# 2CAN_Peripherals.net
KiCad netlist of a schematic drawn in Altium Designer
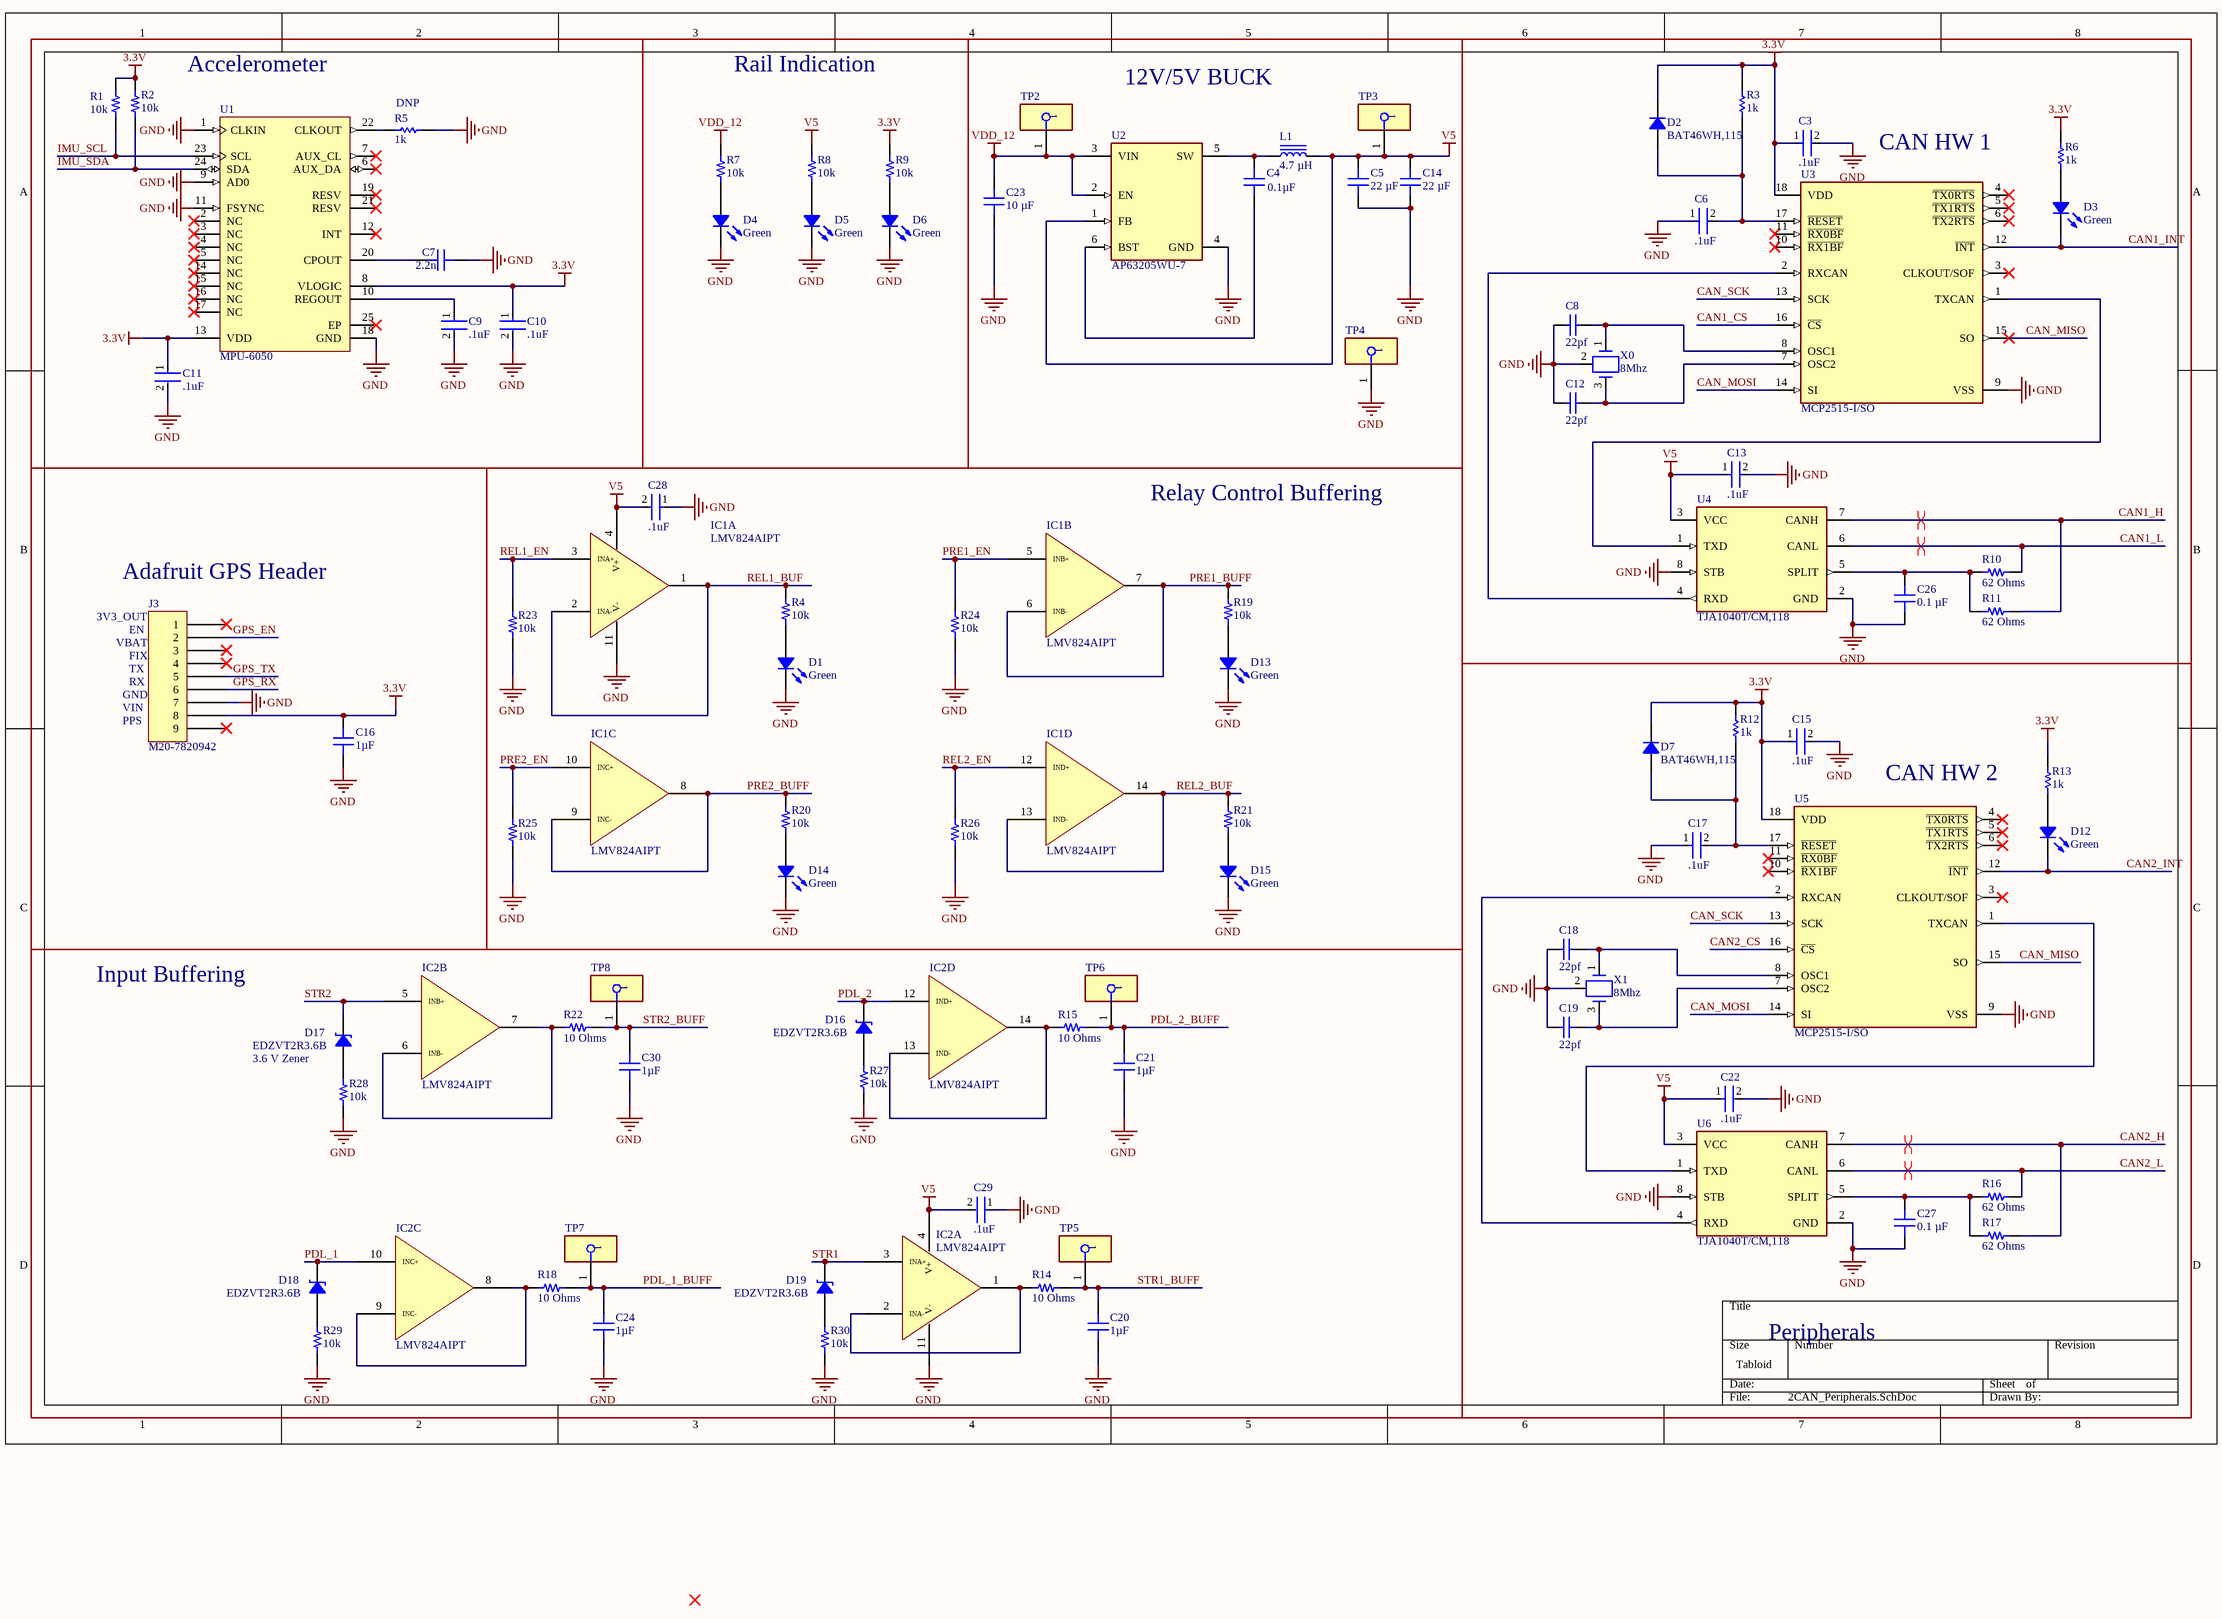
[diagram p0: 2CAN_Peripherals.SchDoc]

(export (version "E")
  (design (tool "Eeschema 10.0.6"))
  (components
    (comp (ref "C3")
      (value ".1uF")
      (footprint "FP-CGA3E-0_3-0_1-IPC_A")
      (description "Cap Ceramic 100nF 50V X7R 10% Pad SMD 0603 +125°C Automotive T/R")
      (fields (field (name "TOLERANCE") "10%") (field (name "VOLTAGE") "50V"))
      (libsource (lib "Altium Content Vault") (part "b4654b650e69147ec39a6b967a45e02"))
    )
    (comp (ref "C4")
      (value "0.1µF")
      (footprint "CAP 0603_1608")
      (description "CAP CER 0.1UF 50V X7R 0603")
      (fields (field (name "PART NUMBER") "06035C104JAT4A"))
      (libsource (lib "Celestial Altium Library - altium_library") (part "Capacitor"))
    )
    (comp (ref "C5")
      (value "22 µF")
      (footprint "CAP 0805_2012")
      (description "CAP CER 22UF 25V X5R 0805")
      (fields (field (name "PART NUMBER") "08053D226MAT2A") (field (name "MANUFACTURER") "KYOCERA AVX"))
      (libsource (lib "Celestial Altium Library - altium_library") (part "Capacitor"))
    )
    (comp (ref "C6")
      (value ".1uF")
      (footprint "FP-CGA3E-0_3-0_1-IPC_A")
      (description "Cap Ceramic 100nF 50V X7R 10% Pad SMD 0603 +125°C Automotive T/R")
      (fields (field (name "TOLERANCE") "10%") (field (name "VOLTAGE") "50V"))
      (libsource (lib "Altium Content Vault") (part "b4654b650e69147ec39a6b967a45e02"))
    )
    (comp (ref "C7")
      (value "2.2n")
      (footprint "CAP 0603_1608")
      (description "CAP CER 0603 2.2NF 16V X7R 10%")
      (fields (field (name "PART NUMBER") "C0603C222K4RECAUTO") (field (name "MANUFACTURER") "KEMET"))
      (libsource (lib "Celestial Altium Library - altium_library") (part "Capacitor"))
    )
    (comp (ref "C8")
      (value "22pf")
      (footprint "CAPC1608X90X35ML10T15")
      (description "Chip Capacitor, 22 pF, +/- 5%, 50 V, -55 to 125 degC, 0603 (1608 Metric), RoHS, Tape and Reel")
      (fields (field (name "MANUFACTURER") "Murata"))
      (libsource (lib "Altium Content Vault") (part "CAP-NP-2"))
    )
    (comp (ref "C9")
      (value ".1uF")
      (footprint "FP-CGA3E-0_3-0_1-IPC_A")
      (description "Cap Ceramic 100nF 50V X7R 10% Pad SMD 0603 +125°C Automotive T/R")
      (fields (field (name "TOLERANCE") "10%") (field (name "VOLTAGE") "50V"))
      (libsource (lib "Altium Content Vault") (part "b4654b650e69147ec39a6b967a45e02"))
    )
    (comp (ref "C10")
      (value ".1uF")
      (footprint "FP-CGA3E-0_3-0_1-IPC_A")
      (description "Cap Ceramic 100nF 50V X7R 10% Pad SMD 0603 +125°C Automotive T/R")
      (fields (field (name "TOLERANCE") "10%") (field (name "VOLTAGE") "50V"))
      (libsource (lib "Altium Content Vault") (part "b4654b650e69147ec39a6b967a45e02"))
    )
    (comp (ref "C11")
      (value ".1uF")
      (footprint "FP-CGA3E-0_3-0_1-IPC_A")
      (description "Cap Ceramic 100nF 50V X7R 10% Pad SMD 0603 +125°C Automotive T/R")
      (fields (field (name "TOLERANCE") "10%") (field (name "VOLTAGE") "50V"))
      (libsource (lib "Altium Content Vault") (part "b4654b650e69147ec39a6b967a45e02"))
    )
    (comp (ref "C12")
      (value "22pf")
      (footprint "CAPC1608X90X35ML10T15")
      (description "Chip Capacitor, 22 pF, +/- 5%, 50 V, -55 to 125 degC, 0603 (1608 Metric), RoHS, Tape and Reel")
      (fields (field (name "MANUFACTURER") "Murata"))
      (libsource (lib "Altium Content Vault") (part "CAP-NP-2"))
    )
    (comp (ref "C13")
      (value ".1uF")
      (footprint "FP-CGA3E-0_3-0_1-IPC_A")
      (description "Cap Ceramic 100nF 50V X7R 10% Pad SMD 0603 +125°C Automotive T/R")
      (fields (field (name "TOLERANCE") "10%") (field (name "VOLTAGE") "50V"))
      (libsource (lib "Altium Content Vault") (part "b4654b650e69147ec39a6b967a45e02"))
    )
    (comp (ref "C14")
      (value "22 µF")
      (footprint "CAP 0805_2012")
      (description "CAP CER 22UF 25V X5R 0805")
      (fields (field (name "PART NUMBER") "08053D226MAT2A") (field (name "MANUFACTURER") "KYOCERA AVX"))
      (libsource (lib "Celestial Altium Library - altium_library") (part "Capacitor"))
    )
    (comp (ref "C15")
      (value ".1uF")
      (footprint "FP-CGA3E-0_3-0_1-IPC_A")
      (description "Cap Ceramic 100nF 50V X7R 10% Pad SMD 0603 +125°C Automotive T/R")
      (fields (field (name "TOLERANCE") "10%") (field (name "VOLTAGE") "50V"))
      (libsource (lib "Altium Content Vault") (part "b4654b650e69147ec39a6b967a45e02"))
    )
    (comp (ref "C16")
      (value "1µF")
      (footprint "CAP 0603_1608")
      (description "CAP CER 1UF 25V X5R 0603")
      (fields (field (name "PART NUMBER") "06033D105MAT2A") (field (name "MANUFACTURER") "AVX Corporation"))
      (libsource (lib "Celestial Altium Library - altium_library") (part "Capacitor"))
    )
    (comp (ref "C17")
      (value ".1uF")
      (footprint "FP-CGA3E-0_3-0_1-IPC_A")
      (description "Cap Ceramic 100nF 50V X7R 10% Pad SMD 0603 +125°C Automotive T/R")
      (fields (field (name "TOLERANCE") "10%") (field (name "VOLTAGE") "50V"))
      (libsource (lib "Altium Content Vault") (part "b4654b650e69147ec39a6b967a45e02"))
    )
    (comp (ref "C18")
      (value "22pf")
      (footprint "CAPC1608X90X35ML10T15")
      (description "Chip Capacitor, 22 pF, +/- 5%, 50 V, -55 to 125 degC, 0603 (1608 Metric), RoHS, Tape and Reel")
      (fields (field (name "MANUFACTURER") "Murata"))
      (libsource (lib "Altium Content Vault") (part "CAP-NP-2"))
    )
    (comp (ref "C19")
      (value "22pf")
      (footprint "CAPC1608X90X35ML10T15")
      (description "Chip Capacitor, 22 pF, +/- 5%, 50 V, -55 to 125 degC, 0603 (1608 Metric), RoHS, Tape and Reel")
      (fields (field (name "MANUFACTURER") "Murata"))
      (libsource (lib "Altium Content Vault") (part "CAP-NP-2"))
    )
    (comp (ref "C20")
      (value "1µF")
      (footprint "CAP 0603_1608")
      (description "CAP CER 1UF 25V X5R 0603")
      (fields (field (name "PART NUMBER") "06033D105MAT2A") (field (name "MANUFACTURER") "AVX Corporation"))
      (libsource (lib "Celestial Altium Library - altium_library") (part "Capacitor"))
    )
    (comp (ref "C21")
      (value "1µF")
      (footprint "CAP 0603_1608")
      (description "CAP CER 1UF 25V X5R 0603")
      (fields (field (name "PART NUMBER") "06033D105MAT2A") (field (name "MANUFACTURER") "AVX Corporation"))
      (libsource (lib "Celestial Altium Library - altium_library") (part "Capacitor"))
    )
    (comp (ref "C22")
      (value ".1uF")
      (footprint "FP-CGA3E-0_3-0_1-IPC_A")
      (description "Cap Ceramic 100nF 50V X7R 10% Pad SMD 0603 +125°C Automotive T/R")
      (fields (field (name "TOLERANCE") "10%") (field (name "VOLTAGE") "50V"))
      (libsource (lib "Altium Content Vault") (part "b4654b650e69147ec39a6b967a45e02"))
    )
    (comp (ref "C23")
      (value "10 µF")
      (footprint "CAP 0805_2012")
      (description "CAP CER 10UF 50V X5R 0805")
      (fields
        (field (name "PART NUMBER") "GRM21BR61H106KE43L")
        (field (name "MANUFACTURER") "Murata Electronics")
      )
      (libsource (lib "Celestial Altium Library - altium_library") (part "Capacitor"))
    )
    (comp (ref "C24")
      (value "1µF")
      (footprint "CAP 0603_1608")
      (description "CAP CER 1UF 25V X5R 0603")
      (fields (field (name "PART NUMBER") "06033D105MAT2A") (field (name "MANUFACTURER") "AVX Corporation"))
      (libsource (lib "Celestial Altium Library - altium_library") (part "Capacitor"))
    )
    (comp (ref "C26")
      (value "0.1 µF")
      (footprint "CAP 0603_1608")
      (description "CAP CER 0.1UF 100V X7R 0603")
      (fields (field (name "PART NUMBER") "HMK107B7104KA-T") (field (name "MANUFACTURER") "Taiyo Yuden"))
      (libsource (lib "Celestial Altium Library - altium_library") (part "Capacitor"))
    )
    (comp (ref "C27")
      (value "0.1 µF")
      (footprint "CAP 0603_1608")
      (description "CAP CER 0.1UF 100V X7R 0603")
      (fields (field (name "PART NUMBER") "HMK107B7104KA-T") (field (name "MANUFACTURER") "Taiyo Yuden"))
      (libsource (lib "Celestial Altium Library - altium_library") (part "Capacitor"))
    )
    (comp (ref "C28")
      (value ".1uF")
      (footprint "FP-CGA3E-0_3-0_1-IPC_A")
      (description "Cap Ceramic 100nF 50V X7R 10% Pad SMD 0603 +125°C Automotive T/R")
      (fields (field (name "TOLERANCE") "10%") (field (name "VOLTAGE") "50V"))
      (libsource (lib "Altium Content Vault") (part "b4654b650e69147ec39a6b967a45e02"))
    )
    (comp (ref "C29")
      (value ".1uF")
      (footprint "FP-CGA3E-0_3-0_1-IPC_A")
      (description "Cap Ceramic 100nF 50V X7R 10% Pad SMD 0603 +125°C Automotive T/R")
      (fields (field (name "TOLERANCE") "10%") (field (name "VOLTAGE") "50V"))
      (libsource (lib "Altium Content Vault") (part "b4654b650e69147ec39a6b967a45e02"))
    )
    (comp (ref "C30")
      (value "1µF")
      (footprint "CAP 0603_1608")
      (description "CAP CER 1UF 25V X5R 0603")
      (fields (field (name "PART NUMBER") "06033D105MAT2A") (field (name "MANUFACTURER") "AVX Corporation"))
      (libsource (lib "Celestial Altium Library - altium_library") (part "Capacitor"))
    )
    (comp (ref "D1")
      (value "Green")
      (footprint "LED 0603_1608 GREEN")
      (description "LED GREEN DIFFUSED SMD")
      (fields
        (field (name "PART NUMBER") "SML-LX0603GW-TR")
        (field (name "MANUFACTURER") "Lumex Opto/Components Inc.")
      )
      (libsource (lib "Celestial Altium Library - altium_library") (part "LED"))
    )
    (comp (ref "D2")
      (value "BAT46WH,115")
      (footprint "SOD123F")
      (description "DIODE SCHOTT 100V 250MA SOD123F")
      (fields (field (name "MANUFACTURER") "Nexperia USA Inc."))
      (libsource (lib "Celestial Altium Library - altium_library") (part "Diode"))
    )
    (comp (ref "D3")
      (value "Green")
      (footprint "LED 0603_1608 GREEN")
      (description "LED GREEN DIFFUSED SMD")
      (fields
        (field (name "PART NUMBER") "SML-LX0603GW-TR")
        (field (name "MANUFACTURER") "Lumex Opto/Components Inc.")
      )
      (libsource (lib "Celestial Altium Library - altium_library") (part "LED"))
    )
    (comp (ref "D4")
      (value "Green")
      (footprint "LED 0603_1608 GREEN")
      (description "LED GREEN DIFFUSED SMD")
      (fields
        (field (name "PART NUMBER") "SML-LX0603GW-TR")
        (field (name "MANUFACTURER") "Lumex Opto/Components Inc.")
      )
      (libsource (lib "Celestial Altium Library - altium_library") (part "LED"))
    )
    (comp (ref "D5")
      (value "Green")
      (footprint "LED 0603_1608 GREEN")
      (description "LED GREEN DIFFUSED SMD")
      (fields
        (field (name "PART NUMBER") "SML-LX0603GW-TR")
        (field (name "MANUFACTURER") "Lumex Opto/Components Inc.")
      )
      (libsource (lib "Celestial Altium Library - altium_library") (part "LED"))
    )
    (comp (ref "D6")
      (value "Green")
      (footprint "LED 0603_1608 GREEN")
      (description "LED GREEN DIFFUSED SMD")
      (fields
        (field (name "PART NUMBER") "SML-LX0603GW-TR")
        (field (name "MANUFACTURER") "Lumex Opto/Components Inc.")
      )
      (libsource (lib "Celestial Altium Library - altium_library") (part "LED"))
    )
    (comp (ref "D7")
      (value "BAT46WH,115")
      (footprint "SOD123F")
      (description "DIODE SCHOTT 100V 250MA SOD123F")
      (fields (field (name "MANUFACTURER") "Nexperia USA Inc."))
      (libsource (lib "Celestial Altium Library - altium_library") (part "Diode"))
    )
    (comp (ref "D12")
      (value "Green")
      (footprint "LED 0603_1608 GREEN")
      (description "LED GREEN DIFFUSED SMD")
      (fields
        (field (name "PART NUMBER") "SML-LX0603GW-TR")
        (field (name "MANUFACTURER") "Lumex Opto/Components Inc.")
      )
      (libsource (lib "Celestial Altium Library - altium_library") (part "LED"))
    )
    (comp (ref "D13")
      (value "Green")
      (footprint "LED 0603_1608 GREEN")
      (description "LED GREEN DIFFUSED SMD")
      (fields
        (field (name "PART NUMBER") "SML-LX0603GW-TR")
        (field (name "MANUFACTURER") "Lumex Opto/Components Inc.")
      )
      (libsource (lib "Celestial Altium Library - altium_library") (part "LED"))
    )
    (comp (ref "D14")
      (value "Green")
      (footprint "LED 0603_1608 GREEN")
      (description "LED GREEN DIFFUSED SMD")
      (fields
        (field (name "PART NUMBER") "SML-LX0603GW-TR")
        (field (name "MANUFACTURER") "Lumex Opto/Components Inc.")
      )
      (libsource (lib "Celestial Altium Library - altium_library") (part "LED"))
    )
    (comp (ref "D15")
      (value "Green")
      (footprint "LED 0603_1608 GREEN")
      (description "LED GREEN DIFFUSED SMD")
      (fields
        (field (name "PART NUMBER") "SML-LX0603GW-TR")
        (field (name "MANUFACTURER") "Lumex Opto/Components Inc.")
      )
      (libsource (lib "Celestial Altium Library - altium_library") (part "LED"))
    )
    (comp (ref "D16")
      (value "EDZVT2R3.6B")
      (footprint "SOD523F")
      (description "DIODE ZENER 3.6V 150MW EMD2")
      (fields (field (name "MANUFACTURER") "Rohm Semiconductor") (field (name "TOLERANCE") "±3%"))
      (libsource (lib "Celestial Altium Library - altium_library") (part "Diode Zener"))
    )
    (comp (ref "D17")
      (value "EDZVT2R3.6B")
      (footprint "SOD523F")
      (description "DIODE ZENER 3.6V 150MW EMD2")
      (fields (field (name "MANUFACTURER") "Rohm Semiconductor") (field (name "TOLERANCE") "±3%"))
      (libsource (lib "Celestial Altium Library - altium_library") (part "Diode Zener"))
    )
    (comp (ref "D18")
      (value "EDZVT2R3.6B")
      (footprint "SOD523F")
      (description "DIODE ZENER 3.6V 150MW EMD2")
      (fields (field (name "MANUFACTURER") "Rohm Semiconductor") (field (name "TOLERANCE") "±3%"))
      (libsource (lib "Celestial Altium Library - altium_library") (part "Diode Zener"))
    )
    (comp (ref "D19")
      (value "EDZVT2R3.6B")
      (footprint "SOD523F")
      (description "DIODE ZENER 3.6V 150MW EMD2")
      (fields (field (name "MANUFACTURER") "Rohm Semiconductor") (field (name "TOLERANCE") "±3%"))
      (libsource (lib "Celestial Altium Library - altium_library") (part "Diode Zener"))
    )
    (comp (ref "IC1")
      (value "LMV824AIPT")
      (footprint "TI TSSOP-14 PW")
      (description "IC OPAMP GP 4 CIRCUIT 14TSSOP")
      (fields (field (name "MANUFACTURER") "STMicroelectronics"))
      (libsource (lib "Celestial Altium Library - altium_library") (part "TI LMV82x 14 PIN"))
    )
    (comp (ref "IC2")
      (value "LMV824AIPT")
      (footprint "TI TSSOP-14 PW")
      (description "IC OPAMP GP 4 CIRCUIT 14TSSOP")
      (fields (field (name "MANUFACTURER") "STMicroelectronics"))
      (libsource (lib "Celestial Altium Library - altium_library") (part "TI LMV82x 14 PIN"))
    )
    (comp (ref "J3")
      (value "M20-7820942")
      (footprint "HARWIN M20-7820945")
      (description "CONN RCPT 9POS 0.1 GOLD PCB")
      (fields (field (name "MANUFACTURER") "Harwin Inc."))
      (libsource (lib "Celestial Altium Library - altium_library") (part "9 Pin"))
    )
    (comp (ref "L1")
      (value "4.7 µH")
      (footprint "WURTH WE-LQS 6045")
      (description "FIXED IND 4.7UH 3.3A 26 MOHM SMD")
      (fields (field (name "PART NUMBER") "74404064047") (field (name "MANUFACTURER") "Würth Elektronik"))
      (libsource (lib "Celestial Altium Library - altium_library") (part "Inductor"))
    )
    (comp (ref "R1")
      (value "10k")
      (footprint "RES 0603_1608")
      (description "RES SMD 10K OHM 0.1% 1/16W 0603")
      (fields
        (field (name "PART NUMBER") "CPF0603B10KE")
        (field (name "MANUFACTURER") "TE Connectivity Passive Product")
      )
      (libsource (lib "Celestial Altium Library - altium_library") (part "Resistor"))
    )
    (comp (ref "R2")
      (value "10k")
      (footprint "RES 0603_1608")
      (description "RES SMD 10K OHM 0.1% 1/16W 0603")
      (fields
        (field (name "PART NUMBER") "CPF0603B10KE")
        (field (name "MANUFACTURER") "TE Connectivity Passive Product")
      )
      (libsource (lib "Celestial Altium Library - altium_library") (part "Resistor"))
    )
    (comp (ref "R3")
      (value "1k")
      (footprint "RESC1608X55X30LL15T15")
      (fields (field (name "PART NUMBER") "ERJ-3EKF1001V") (field (name "MANUFACTURER") "Panasonic"))
      (libsource (lib "Altium Content Vault") (part "RES"))
    )
    (comp (ref "R4")
      (value "10k")
      (footprint "RES 0603_1608")
      (description "RES SMD 10K OHM 0.1% 1/16W 0603")
      (fields
        (field (name "PART NUMBER") "CPF0603B10KE")
        (field (name "MANUFACTURER") "TE Connectivity Passive Product")
      )
      (libsource (lib "Celestial Altium Library - altium_library") (part "Resistor"))
    )
    (comp (ref "R5")
      (value "1k")
      (footprint "RESC1608X55X30LL15T15")
      (fields (field (name "PART NUMBER") "ERJ-3EKF1001V") (field (name "MANUFACTURER") "Panasonic"))
      (libsource (lib "Altium Content Vault") (part "RES"))
    )
    (comp (ref "R6")
      (value "1k")
      (footprint "RESC1608X55X30LL15T15")
      (fields (field (name "PART NUMBER") "ERJ-3EKF1001V") (field (name "MANUFACTURER") "Panasonic"))
      (libsource (lib "Altium Content Vault") (part "RES"))
    )
    (comp (ref "R7")
      (value "10k")
      (footprint "RES 0603_1608")
      (description "RES SMD 10K OHM 0.1% 1/16W 0603")
      (fields
        (field (name "PART NUMBER") "CPF0603B10KE")
        (field (name "MANUFACTURER") "TE Connectivity Passive Product")
      )
      (libsource (lib "Celestial Altium Library - altium_library") (part "Resistor"))
    )
    (comp (ref "R8")
      (value "10k")
      (footprint "RES 0603_1608")
      (description "RES SMD 10K OHM 0.1% 1/16W 0603")
      (fields
        (field (name "PART NUMBER") "CPF0603B10KE")
        (field (name "MANUFACTURER") "TE Connectivity Passive Product")
      )
      (libsource (lib "Celestial Altium Library - altium_library") (part "Resistor"))
    )
    (comp (ref "R9")
      (value "10k")
      (footprint "RES 0603_1608")
      (description "RES SMD 10K OHM 0.1% 1/16W 0603")
      (fields
        (field (name "PART NUMBER") "CPF0603B10KE")
        (field (name "MANUFACTURER") "TE Connectivity Passive Product")
      )
      (libsource (lib "Celestial Altium Library - altium_library") (part "Resistor"))
    )
    (comp (ref "R10")
      (value "62 Ohms")
      (footprint "RES 0603_1608")
      (description "HIGH ANTI-SURGE THICK FILM CHIP")
      (fields (field (name "PART NUMBER") "SDR03EZPJ620") (field (name "MANUFACTURER") "Rohm Semiconductor"))
      (libsource (lib "Celestial Altium Library - altium_library") (part "Resistor"))
    )
    (comp (ref "R11")
      (value "62 Ohms")
      (footprint "RES 0603_1608")
      (description "HIGH ANTI-SURGE THICK FILM CHIP")
      (fields (field (name "PART NUMBER") "SDR03EZPJ620") (field (name "MANUFACTURER") "Rohm Semiconductor"))
      (libsource (lib "Celestial Altium Library - altium_library") (part "Resistor"))
    )
    (comp (ref "R12")
      (value "1k")
      (footprint "RESC1608X55X30LL15T15")
      (fields (field (name "PART NUMBER") "ERJ-3EKF1001V") (field (name "MANUFACTURER") "Panasonic"))
      (libsource (lib "Altium Content Vault") (part "RES"))
    )
    (comp (ref "R13")
      (value "1k")
      (footprint "RESC1608X55X30LL15T15")
      (fields (field (name "PART NUMBER") "ERJ-3EKF1001V") (field (name "MANUFACTURER") "Panasonic"))
      (libsource (lib "Altium Content Vault") (part "RES"))
    )
    (comp (ref "R14")
      (value "10 Ohms")
      (footprint "RES 0603_1608")
      (description "RESA-AS 0603 10R 1% 100MW TC100")
      (fields (field (name "PART NUMBER") "CR0603AFX-10R0EAS") (field (name "MANUFACTURER") "Bourns Inc."))
      (libsource (lib "Celestial Altium Library - altium_library") (part "Resistor"))
    )
    (comp (ref "R15")
      (value "10 Ohms")
      (footprint "RES 0603_1608")
      (description "RESA-AS 0603 10R 1% 100MW TC100")
      (fields (field (name "PART NUMBER") "CR0603AFX-10R0EAS") (field (name "MANUFACTURER") "Bourns Inc."))
      (libsource (lib "Celestial Altium Library - altium_library") (part "Resistor"))
    )
    (comp (ref "R16")
      (value "62 Ohms")
      (footprint "RES 0603_1608")
      (description "HIGH ANTI-SURGE THICK FILM CHIP")
      (fields (field (name "PART NUMBER") "SDR03EZPJ620") (field (name "MANUFACTURER") "Rohm Semiconductor"))
      (libsource (lib "Celestial Altium Library - altium_library") (part "Resistor"))
    )
    (comp (ref "R17")
      (value "62 Ohms")
      (footprint "RES 0603_1608")
      (description "HIGH ANTI-SURGE THICK FILM CHIP")
      (fields (field (name "PART NUMBER") "SDR03EZPJ620") (field (name "MANUFACTURER") "Rohm Semiconductor"))
      (libsource (lib "Celestial Altium Library - altium_library") (part "Resistor"))
    )
    (comp (ref "R18")
      (value "10 Ohms")
      (footprint "RES 0603_1608")
      (description "RESA-AS 0603 10R 1% 100MW TC100")
      (fields (field (name "PART NUMBER") "CR0603AFX-10R0EAS") (field (name "MANUFACTURER") "Bourns Inc."))
      (libsource (lib "Celestial Altium Library - altium_library") (part "Resistor"))
    )
    (comp (ref "R19")
      (value "10k")
      (footprint "RES 0603_1608")
      (description "RES SMD 10K OHM 0.1% 1/16W 0603")
      (fields
        (field (name "PART NUMBER") "CPF0603B10KE")
        (field (name "MANUFACTURER") "TE Connectivity Passive Product")
      )
      (libsource (lib "Celestial Altium Library - altium_library") (part "Resistor"))
    )
    (comp (ref "R20")
      (value "10k")
      (footprint "RES 0603_1608")
      (description "RES SMD 10K OHM 0.1% 1/16W 0603")
      (fields
        (field (name "PART NUMBER") "CPF0603B10KE")
        (field (name "MANUFACTURER") "TE Connectivity Passive Product")
      )
      (libsource (lib "Celestial Altium Library - altium_library") (part "Resistor"))
    )
    (comp (ref "R21")
      (value "10k")
      (footprint "RES 0603_1608")
      (description "RES SMD 10K OHM 0.1% 1/16W 0603")
      (fields
        (field (name "PART NUMBER") "CPF0603B10KE")
        (field (name "MANUFACTURER") "TE Connectivity Passive Product")
      )
      (libsource (lib "Celestial Altium Library - altium_library") (part "Resistor"))
    )
    (comp (ref "R22")
      (value "10 Ohms")
      (footprint "RES 0603_1608")
      (description "RESA-AS 0603 10R 1% 100MW TC100")
      (fields (field (name "PART NUMBER") "CR0603AFX-10R0EAS") (field (name "MANUFACTURER") "Bourns Inc."))
      (libsource (lib "Celestial Altium Library - altium_library") (part "Resistor"))
    )
    (comp (ref "R23")
      (value "10k")
      (footprint "RES 0603_1608")
      (description "RES SMD 10K OHM 0.1% 1/16W 0603")
      (fields
        (field (name "PART NUMBER") "CPF0603B10KE")
        (field (name "MANUFACTURER") "TE Connectivity Passive Product")
      )
      (libsource (lib "Celestial Altium Library - altium_library") (part "Resistor"))
    )
    (comp (ref "R24")
      (value "10k")
      (footprint "RES 0603_1608")
      (description "RES SMD 10K OHM 0.1% 1/16W 0603")
      (fields
        (field (name "PART NUMBER") "CPF0603B10KE")
        (field (name "MANUFACTURER") "TE Connectivity Passive Product")
      )
      (libsource (lib "Celestial Altium Library - altium_library") (part "Resistor"))
    )
    (comp (ref "R25")
      (value "10k")
      (footprint "RES 0603_1608")
      (description "RES SMD 10K OHM 0.1% 1/16W 0603")
      (fields
        (field (name "PART NUMBER") "CPF0603B10KE")
        (field (name "MANUFACTURER") "TE Connectivity Passive Product")
      )
      (libsource (lib "Celestial Altium Library - altium_library") (part "Resistor"))
    )
    (comp (ref "R26")
      (value "10k")
      (footprint "RES 0603_1608")
      (description "RES SMD 10K OHM 0.1% 1/16W 0603")
      (fields
        (field (name "PART NUMBER") "CPF0603B10KE")
        (field (name "MANUFACTURER") "TE Connectivity Passive Product")
      )
      (libsource (lib "Celestial Altium Library - altium_library") (part "Resistor"))
    )
    (comp (ref "R27")
      (value "10k")
      (footprint "RES 0603_1608")
      (description "RES SMD 10K OHM 0.1% 1/16W 0603")
      (fields
        (field (name "PART NUMBER") "CPF0603B10KE")
        (field (name "MANUFACTURER") "TE Connectivity Passive Product")
      )
      (libsource (lib "Celestial Altium Library - altium_library") (part "Resistor"))
    )
    (comp (ref "R28")
      (value "10k")
      (footprint "RES 0603_1608")
      (description "RES SMD 10K OHM 0.1% 1/16W 0603")
      (fields
        (field (name "PART NUMBER") "CPF0603B10KE")
        (field (name "MANUFACTURER") "TE Connectivity Passive Product")
      )
      (libsource (lib "Celestial Altium Library - altium_library") (part "Resistor"))
    )
    (comp (ref "R29")
      (value "10k")
      (footprint "RES 0603_1608")
      (description "RES SMD 10K OHM 0.1% 1/16W 0603")
      (fields
        (field (name "PART NUMBER") "CPF0603B10KE")
        (field (name "MANUFACTURER") "TE Connectivity Passive Product")
      )
      (libsource (lib "Celestial Altium Library - altium_library") (part "Resistor"))
    )
    (comp (ref "R30")
      (value "10k")
      (footprint "RES 0603_1608")
      (description "RES SMD 10K OHM 0.1% 1/16W 0603")
      (fields
        (field (name "PART NUMBER") "CPF0603B10KE")
        (field (name "MANUFACTURER") "TE Connectivity Passive Product")
      )
      (libsource (lib "Celestial Altium Library - altium_library") (part "Resistor"))
    )
    (comp (ref "TP2")
      (value "S2761-46R")
      (footprint "FP-S2761-46R-MFG")
      (description "PC TEST POINT NATURAL")
      (libsource (lib "Altium Content Vault") (part "98815daf2f2c152b0c43f5ab9800df6"))
    )
    (comp (ref "TP3")
      (value "S2761-46R")
      (footprint "FP-S2761-46R-MFG")
      (description "PC TEST POINT NATURAL")
      (libsource (lib "Altium Content Vault") (part "98815daf2f2c152b0c43f5ab9800df6"))
    )
    (comp (ref "TP4")
      (value "S2761-46R")
      (footprint "FP-S2761-46R-MFG")
      (description "PC TEST POINT NATURAL")
      (libsource (lib "Altium Content Vault") (part "98815daf2f2c152b0c43f5ab9800df6"))
    )
    (comp (ref "TP5")
      (value "S2761-46R")
      (footprint "FP-S2761-46R-MFG")
      (description "PC TEST POINT NATURAL")
      (libsource (lib "Altium Content Vault") (part "98815daf2f2c152b0c43f5ab9800df6"))
    )
    (comp (ref "TP6")
      (value "S2761-46R")
      (footprint "FP-S2761-46R-MFG")
      (description "PC TEST POINT NATURAL")
      (libsource (lib "Altium Content Vault") (part "98815daf2f2c152b0c43f5ab9800df6"))
    )
    (comp (ref "TP7")
      (value "S2761-46R")
      (footprint "FP-S2761-46R-MFG")
      (description "PC TEST POINT NATURAL")
      (libsource (lib "Altium Content Vault") (part "98815daf2f2c152b0c43f5ab9800df6"))
    )
    (comp (ref "TP8")
      (value "S2761-46R")
      (footprint "FP-S2761-46R-MFG")
      (description "PC TEST POINT NATURAL")
      (libsource (lib "Altium Content Vault") (part "98815daf2f2c152b0c43f5ab9800df6"))
    )
    (comp (ref "U1")
      (value "MPU-6050")
      (footprint "IS-QFN-24_V")
      (fields (field (name "MANUFACTURER") "InvenSense"))
      (libsource (lib "Altium Content Vault") (part "IS-MPU-6050-QFN-24"))
    )
    (comp (ref "U2")
      (value "AP63205WU-7")
      (footprint "FP-TSOT26-MFG")
      (description "IC REG BUCK 5V 2A TSOT26")
      (fields
        (field (name "MANUFACTURER") "Diodes Inc.")
        (field (name "OCTOPART") "https://octopart.com/ap63205wu-7-diodes+inc.-98099551")
      )
      (libsource (lib "Altium Content Vault") (part "029bc9fbfa4a99dbb8b3a24c2adb655"))
    )
    (comp (ref "U3")
      (value "MCP2515-I/SO")
      (footprint "FP-C04-051-IPC_C")
      (description "IC CAN CONTROLLER W/SPI 18SOIC")
      (fields
        (field (name "MANUFACTURER") "Microchip")
        (field (name "OCTOPART") "https://octopart.com/mcp2515-i%2Fso-microchip-430187")
      )
      (libsource (lib "Altium Content Vault") (part "1c78ea6ff576bac94664e2637e1b479"))
    )
    (comp (ref "U4")
      (value "TJA1040T/CM,118")
      (footprint "FP-SOT96-1-MFG")
      (description "IC TRANSCEIVER HALF 1/1 8SO")
      (libsource (lib "Altium Content Vault") (part "5cc2716200bfea26bb0dabd3acf5976"))
    )
    (comp (ref "U5")
      (value "MCP2515-I/SO")
      (footprint "FP-C04-051-IPC_C")
      (description "IC CAN CONTROLLER W/SPI 18SOIC")
      (fields
        (field (name "MANUFACTURER") "Microchip")
        (field (name "OCTOPART") "https://octopart.com/mcp2515-i%2Fso-microchip-430187")
      )
      (libsource (lib "Altium Content Vault") (part "1c78ea6ff576bac94664e2637e1b479"))
    )
    (comp (ref "U6")
      (value "TJA1040T/CM,118")
      (footprint "FP-SOT96-1-MFG")
      (description "IC TRANSCEIVER HALF 1/1 8SO")
      (libsource (lib "Altium Content Vault") (part "5cc2716200bfea26bb0dabd3acf5976"))
    )
    (comp (ref "X0")
      (value "8Mhz")
      (footprint "ECS-4X-3IL")
      (description "CRYSTAL 8.00 MHZ 20PF 49US")
      (fields (field (name "PARTNUMBER") "ECS-80-20-4X") (field (name "MANUFACTURER") "ECS"))
      (libsource (lib "Altium Content Vault") (part "ECS-ECS-XX-20-4X"))
    )
    (comp (ref "X1")
      (value "8Mhz")
      (footprint "ECS-4X-3IL")
      (description "CRYSTAL 8.00 MHZ 20PF 49US")
      (fields (field (name "PARTNUMBER") "ECS-80-20-4X") (field (name "MANUFACTURER") "ECS"))
      (libsource (lib "Altium Content Vault") (part "ECS-ECS-XX-20-4X"))
    )
  )
  (nets
    (net (code "1") (name "/CAN1_CS") (class "Default")
      (node (ref "U3") (pin "16") (pinfunction "~{CS}_16") (pintype "input"))
    )
    (net (code "2") (name "/CAN1_H") (class "Default")
      (node (ref "R11") (pin "2") (pinfunction "2_2") (pintype "passive"))
      (node (ref "U4") (pin "7") (pinfunction "CANH_7") (pintype "passive"))
    )
    (net (code "3") (name "/CAN1_INT") (class "Default")
      (node (ref "D3") (pin "2") (pinfunction "2_2") (pintype "passive"))
      (node (ref "U3") (pin "12") (pinfunction "~{INT}_12") (pintype "output"))
    )
    (net (code "4") (name "/CAN1_L") (class "Default")
      (node (ref "R10") (pin "2") (pinfunction "2_2") (pintype "passive"))
      (node (ref "U4") (pin "6") (pinfunction "CANL_6") (pintype "passive"))
    )
    (net (code "5") (name "/CAN2_CS") (class "Default")
      (node (ref "U5") (pin "16") (pinfunction "~{CS}_16") (pintype "input"))
    )
    (net (code "6") (name "/CAN2_H") (class "Default")
      (node (ref "R17") (pin "2") (pinfunction "2_2") (pintype "passive"))
      (node (ref "U6") (pin "7") (pinfunction "CANH_7") (pintype "passive"))
    )
    (net (code "7") (name "/CAN2_INT") (class "Default")
      (node (ref "D12") (pin "2") (pinfunction "2_2") (pintype "passive"))
      (node (ref "U5") (pin "12") (pinfunction "~{INT}_12") (pintype "output"))
    )
    (net (code "8") (name "/CAN2_L") (class "Default")
      (node (ref "R16") (pin "2") (pinfunction "2_2") (pintype "passive"))
      (node (ref "U6") (pin "6") (pinfunction "CANL_6") (pintype "passive"))
    )
    (net (code "9") (name "/CAN_MISO") (class "Default")
      (node (ref "U3") (pin "15") (pinfunction "SO_15") (pintype "output"))
      (node (ref "U5") (pin "15") (pinfunction "SO_15") (pintype "output"))
    )
    (net (code "10") (name "/CAN_MOSI") (class "Default")
      (node (ref "U3") (pin "14") (pinfunction "SI_14") (pintype "input"))
      (node (ref "U5") (pin "14") (pinfunction "SI_14") (pintype "input"))
    )
    (net (code "11") (name "/CAN_SCK") (class "Default")
      (node (ref "U3") (pin "13") (pinfunction "SCK_13") (pintype "input"))
      (node (ref "U5") (pin "13") (pinfunction "SCK_13") (pintype "input"))
    )
    (net (code "12") (name "/GPS_EN") (class "Default")
      (node (ref "J3") (pin "2") (pinfunction "2_2") (pintype "passive"))
    )
    (net (code "13") (name "/GPS_RX") (class "Default")
      (node (ref "J3") (pin "6") (pinfunction "6_6") (pintype "passive"))
    )
    (net (code "14") (name "/GPS_TX") (class "Default")
      (node (ref "J3") (pin "5") (pinfunction "5_5") (pintype "passive"))
    )
    (net (code "15") (name "/IMU_SCL") (class "Default")
      (node (ref "R1") (pin "1") (pinfunction "1_1") (pintype "passive"))
      (node (ref "U1") (pin "23") (pinfunction "SCL_23") (pintype "input"))
    )
    (net (code "16") (name "/IMU_SDA") (class "Default")
      (node (ref "R2") (pin "1") (pinfunction "1_1") (pintype "passive"))
      (node (ref "U1") (pin "24") (pinfunction "SDA_24") (pintype "bidirectional"))
    )
    (net (code "17") (name "/PDL_1") (class "Default")
      (node (ref "D18") (pin "2") (pinfunction "2_2") (pintype "passive"))
      (node (ref "IC2") (pin "10") (pinfunction "INC+_10") (pintype "passive"))
    )
    (net (code "18") (name "/PDL_1_BUFF") (class "Default")
      (node (ref "C24") (pin "2") (pinfunction "2_2") (pintype "passive"))
      (node (ref "R18") (pin "2") (pinfunction "2_2") (pintype "passive"))
      (node (ref "TP7") (pin "1") (pinfunction "1_1") (pintype "passive"))
    )
    (net (code "19") (name "/PDL_2") (class "Default")
      (node (ref "D16") (pin "2") (pinfunction "2_2") (pintype "passive"))
      (node (ref "IC2") (pin "12") (pinfunction "IND+_12") (pintype "passive"))
    )
    (net (code "20") (name "/PDL_2_BUFF") (class "Default")
      (node (ref "C21") (pin "2") (pinfunction "2_2") (pintype "passive"))
      (node (ref "R15") (pin "2") (pinfunction "2_2") (pintype "passive"))
      (node (ref "TP6") (pin "1") (pinfunction "1_1") (pintype "passive"))
    )
    (net (code "21") (name "/PRE1_BUFF") (class "Default")
      (node (ref "IC1") (pin "6") (pinfunction "INB-_6") (pintype "passive"))
      (node (ref "IC1") (pin "7") (pinfunction "OUTB_7") (pintype "passive"))
      (node (ref "R19") (pin "2") (pinfunction "2_2") (pintype "passive"))
    )
    (net (code "22") (name "/PRE1_EN") (class "Default")
      (node (ref "IC1") (pin "5") (pinfunction "INB+_5") (pintype "passive"))
      (node (ref "R24") (pin "2") (pinfunction "2_2") (pintype "passive"))
    )
    (net (code "23") (name "/PRE2_BUFF") (class "Default")
      (node (ref "IC1") (pin "8") (pinfunction "OUTC_8") (pintype "passive"))
      (node (ref "IC1") (pin "9") (pinfunction "INC-_9") (pintype "passive"))
      (node (ref "R20") (pin "2") (pinfunction "2_2") (pintype "passive"))
    )
    (net (code "24") (name "/PRE2_EN") (class "Default")
      (node (ref "IC1") (pin "10") (pinfunction "INC+_10") (pintype "passive"))
      (node (ref "R25") (pin "2") (pinfunction "2_2") (pintype "passive"))
    )
    (net (code "25") (name "/REL1_BUF") (class "Default")
      (node (ref "IC1") (pin "1") (pinfunction "OUT_1") (pintype "passive"))
      (node (ref "IC1") (pin "2") (pinfunction "INA-_2") (pintype "passive"))
      (node (ref "R4") (pin "2") (pinfunction "2_2") (pintype "passive"))
    )
    (net (code "26") (name "/REL1_EN") (class "Default")
      (node (ref "IC1") (pin "3") (pinfunction "INA+_3") (pintype "passive"))
      (node (ref "R23") (pin "2") (pinfunction "2_2") (pintype "passive"))
    )
    (net (code "27") (name "/REL2_BUF") (class "Default")
      (node (ref "IC1") (pin "13") (pinfunction "IND-_13") (pintype "passive"))
      (node (ref "IC1") (pin "14") (pinfunction "OUTD_14") (pintype "passive"))
      (node (ref "R21") (pin "2") (pinfunction "2_2") (pintype "passive"))
    )
    (net (code "28") (name "/REL2_EN") (class "Default")
      (node (ref "IC1") (pin "12") (pinfunction "IND+_12") (pintype "passive"))
      (node (ref "R26") (pin "2") (pinfunction "2_2") (pintype "passive"))
    )
    (net (code "29") (name "/STR1") (class "Default")
      (node (ref "D19") (pin "2") (pinfunction "2_2") (pintype "passive"))
      (node (ref "IC2") (pin "3") (pinfunction "INA+_3") (pintype "passive"))
    )
    (net (code "30") (name "/STR1_BUFF") (class "Default")
      (node (ref "C20") (pin "2") (pinfunction "2_2") (pintype "passive"))
      (node (ref "R14") (pin "2") (pinfunction "2_2") (pintype "passive"))
      (node (ref "TP5") (pin "1") (pinfunction "1_1") (pintype "passive"))
    )
    (net (code "31") (name "/STR2") (class "Default")
      (node (ref "D17") (pin "2") (pinfunction "2_2") (pintype "passive"))
      (node (ref "IC2") (pin "5") (pinfunction "INB+_5") (pintype "passive"))
    )
    (net (code "32") (name "/STR2_BUFF") (class "Default")
      (node (ref "C30") (pin "2") (pinfunction "2_2") (pintype "passive"))
      (node (ref "R22") (pin "2") (pinfunction "2_2") (pintype "passive"))
      (node (ref "TP8") (pin "1") (pinfunction "1_1") (pintype "passive"))
    )
    (net (code "33") (name "3.3V") (class "Default")
      (node (ref "C10") (pin "1") (pinfunction "1_1") (pintype "passive"))
      (node (ref "C11") (pin "1") (pinfunction "1_1") (pintype "passive"))
      (node (ref "C15") (pin "1") (pinfunction "1_1") (pintype "passive"))
      (node (ref "C16") (pin "2") (pinfunction "2_2") (pintype "passive"))
      (node (ref "C3") (pin "1") (pinfunction "1_1") (pintype "passive"))
      (node (ref "D2") (pin "2") (pinfunction "2_2") (pintype "passive"))
      (node (ref "D7") (pin "2") (pinfunction "2_2") (pintype "passive"))
      (node (ref "J3") (pin "8") (pinfunction "8_8") (pintype "passive"))
      (node (ref "R1") (pin "2") (pinfunction "2_2") (pintype "passive"))
      (node (ref "R12") (pin "1") (pinfunction "1_1") (pintype "passive"))
      (node (ref "R13") (pin "1") (pinfunction "1_1") (pintype "passive"))
      (node (ref "R2") (pin "2") (pinfunction "2_2") (pintype "passive"))
      (node (ref "R3") (pin "1") (pinfunction "1_1") (pintype "passive"))
      (node (ref "R6") (pin "1") (pinfunction "1_1") (pintype "passive"))
      (node (ref "R9") (pin "2") (pinfunction "2_2") (pintype "passive"))
      (node (ref "U1") (pin "13") (pinfunction "VDD_13") (pintype "power_in"))
      (node (ref "U1") (pin "8") (pinfunction "VLOGIC_8") (pintype "power_in"))
      (node (ref "U3") (pin "18") (pinfunction "VDD_18") (pintype "power_in"))
      (node (ref "U5") (pin "18") (pinfunction "VDD_18") (pintype "power_in"))
    )
    (net (code "34") (name "GND") (class "Default")
      (node (ref "C10") (pin "2") (pinfunction "2_2") (pintype "passive"))
      (node (ref "C11") (pin "2") (pinfunction "2_2") (pintype "passive"))
      (node (ref "C12") (pin "1") (pinfunction "1_1") (pintype "passive"))
      (node (ref "C13") (pin "2") (pinfunction "2_2") (pintype "passive"))
      (node (ref "C14") (pin "1") (pinfunction "1_1") (pintype "passive"))
      (node (ref "C15") (pin "2") (pinfunction "2_2") (pintype "passive"))
      (node (ref "C16") (pin "1") (pinfunction "1_1") (pintype "passive"))
      (node (ref "C17") (pin "1") (pinfunction "1_1") (pintype "passive"))
      (node (ref "C18") (pin "1") (pinfunction "1_1") (pintype "passive"))
      (node (ref "C19") (pin "1") (pinfunction "1_1") (pintype "passive"))
      (node (ref "C20") (pin "1") (pinfunction "1_1") (pintype "passive"))
      (node (ref "C21") (pin "1") (pinfunction "1_1") (pintype "passive"))
      (node (ref "C22") (pin "2") (pinfunction "2_2") (pintype "passive"))
      (node (ref "C23") (pin "1") (pinfunction "1_1") (pintype "passive"))
      (node (ref "C24") (pin "1") (pinfunction "1_1") (pintype "passive"))
      (node (ref "C26") (pin "1") (pinfunction "1_1") (pintype "passive"))
      (node (ref "C27") (pin "1") (pinfunction "1_1") (pintype "passive"))
      (node (ref "C28") (pin "1") (pinfunction "1_1") (pintype "passive"))
      (node (ref "C29") (pin "1") (pinfunction "1_1") (pintype "passive"))
      (node (ref "C3") (pin "2") (pinfunction "2_2") (pintype "passive"))
      (node (ref "C30") (pin "1") (pinfunction "1_1") (pintype "passive"))
      (node (ref "C5") (pin "1") (pinfunction "1_1") (pintype "passive"))
      (node (ref "C6") (pin "1") (pinfunction "1_1") (pintype "passive"))
      (node (ref "C7") (pin "2") (pinfunction "2_2") (pintype "passive"))
      (node (ref "C8") (pin "1") (pinfunction "1_1") (pintype "passive"))
      (node (ref "C9") (pin "2") (pinfunction "2_2") (pintype "passive"))
      (node (ref "D1") (pin "2") (pinfunction "2_2") (pintype "passive"))
      (node (ref "D13") (pin "2") (pinfunction "2_2") (pintype "passive"))
      (node (ref "D14") (pin "2") (pinfunction "2_2") (pintype "passive"))
      (node (ref "D15") (pin "2") (pinfunction "2_2") (pintype "passive"))
      (node (ref "D4") (pin "2") (pinfunction "2_2") (pintype "passive"))
      (node (ref "D5") (pin "2") (pinfunction "2_2") (pintype "passive"))
      (node (ref "D6") (pin "2") (pinfunction "2_2") (pintype "passive"))
      (node (ref "IC1") (pin "11") (pinfunction "V-_11") (pintype "power_in"))
      (node (ref "IC2") (pin "11") (pinfunction "V-_11") (pintype "power_in"))
      (node (ref "J3") (pin "7") (pinfunction "7_7") (pintype "passive"))
      (node (ref "R23") (pin "1") (pinfunction "1_1") (pintype "passive"))
      (node (ref "R24") (pin "1") (pinfunction "1_1") (pintype "passive"))
      (node (ref "R25") (pin "1") (pinfunction "1_1") (pintype "passive"))
      (node (ref "R26") (pin "1") (pinfunction "1_1") (pintype "passive"))
      (node (ref "R27") (pin "1") (pinfunction "1_1") (pintype "passive"))
      (node (ref "R28") (pin "1") (pinfunction "1_1") (pintype "passive"))
      (node (ref "R29") (pin "1") (pinfunction "1_1") (pintype "passive"))
      (node (ref "R30") (pin "1") (pinfunction "1_1") (pintype "passive"))
      (node (ref "R5") (pin "2") (pinfunction "2_2") (pintype "passive"))
      (node (ref "TP4") (pin "1") (pinfunction "1_1") (pintype "passive"))
      (node (ref "U1") (pin "1") (pinfunction "CLKIN_1") (pintype "input"))
      (node (ref "U1") (pin "11") (pinfunction "FSYNC_11") (pintype "input"))
      (node (ref "U1") (pin "18") (pinfunction "GND_18") (pintype "power_in"))
      (node (ref "U1") (pin "9") (pinfunction "AD0_9") (pintype "input"))
      (node (ref "U2") (pin "4") (pinfunction "GND_4") (pintype "power_in"))
      (node (ref "U3") (pin "9") (pinfunction "VSS_9") (pintype "power_in"))
      (node (ref "U4") (pin "2") (pinfunction "GND_2") (pintype "power_in"))
      (node (ref "U4") (pin "8") (pinfunction "STB_8") (pintype "input"))
      (node (ref "U5") (pin "9") (pinfunction "VSS_9") (pintype "power_in"))
      (node (ref "U6") (pin "2") (pinfunction "GND_2") (pintype "power_in"))
      (node (ref "U6") (pin "8") (pinfunction "STB_8") (pintype "input"))
      (node (ref "X0") (pin "2") (pinfunction "2_2") (pintype "passive"))
      (node (ref "X1") (pin "2") (pinfunction "2_2") (pintype "passive"))
    )
    (net (code "35") (name "Net-(D1-Pad1)") (class "Default")
      (node (ref "D1") (pin "1") (pinfunction "1_1") (pintype "passive"))
      (node (ref "R4") (pin "1") (pinfunction "1_1") (pintype "passive"))
    )
    (net (code "36") (name "Net-(D3-Pad1)") (class "Default")
      (node (ref "D3") (pin "1") (pinfunction "1_1") (pintype "passive"))
      (node (ref "R6") (pin "2") (pinfunction "2_2") (pintype "passive"))
    )
    (net (code "37") (name "Net-(D4-Pad1)") (class "Default")
      (node (ref "D4") (pin "1") (pinfunction "1_1") (pintype "passive"))
      (node (ref "R7") (pin "1") (pinfunction "1_1") (pintype "passive"))
    )
    (net (code "38") (name "Net-(D5-Pad1)") (class "Default")
      (node (ref "D5") (pin "1") (pinfunction "1_1") (pintype "passive"))
      (node (ref "R8") (pin "1") (pinfunction "1_1") (pintype "passive"))
    )
    (net (code "39") (name "Net-(D6-Pad1)") (class "Default")
      (node (ref "D6") (pin "1") (pinfunction "1_1") (pintype "passive"))
      (node (ref "R9") (pin "1") (pinfunction "1_1") (pintype "passive"))
    )
    (net (code "40") (name "Net-(D12-Pad1)") (class "Default")
      (node (ref "D12") (pin "1") (pinfunction "1_1") (pintype "passive"))
      (node (ref "R13") (pin "2") (pinfunction "2_2") (pintype "passive"))
    )
    (net (code "41") (name "Net-(D13-Pad1)") (class "Default")
      (node (ref "D13") (pin "1") (pinfunction "1_1") (pintype "passive"))
      (node (ref "R19") (pin "1") (pinfunction "1_1") (pintype "passive"))
    )
    (net (code "42") (name "Net-(D14-Pad1)") (class "Default")
      (node (ref "D14") (pin "1") (pinfunction "1_1") (pintype "passive"))
      (node (ref "R20") (pin "1") (pinfunction "1_1") (pintype "passive"))
    )
    (net (code "43") (name "Net-(D15-Pad1)") (class "Default")
      (node (ref "D15") (pin "1") (pinfunction "1_1") (pintype "passive"))
      (node (ref "R21") (pin "1") (pinfunction "1_1") (pintype "passive"))
    )
    (net (code "44") (name "Net-(D16-Pad1)") (class "Default")
      (node (ref "D16") (pin "1") (pinfunction "1_1") (pintype "passive"))
      (node (ref "R27") (pin "2") (pinfunction "2_2") (pintype "passive"))
    )
    (net (code "45") (name "Net-(D17-Pad1)") (class "Default")
      (node (ref "D17") (pin "1") (pinfunction "1_1") (pintype "passive"))
      (node (ref "R28") (pin "2") (pinfunction "2_2") (pintype "passive"))
    )
    (net (code "46") (name "Net-(D18-Pad1)") (class "Default")
      (node (ref "D18") (pin "1") (pinfunction "1_1") (pintype "passive"))
      (node (ref "R29") (pin "2") (pinfunction "2_2") (pintype "passive"))
    )
    (net (code "47") (name "Net-(D19-Pad1)") (class "Default")
      (node (ref "D19") (pin "1") (pinfunction "1_1") (pintype "passive"))
      (node (ref "R30") (pin "2") (pinfunction "2_2") (pintype "passive"))
    )
    (net (code "48") (name "Net-(IC2A-INA-)") (class "Default")
      (node (ref "IC2") (pin "1") (pinfunction "OUT_1") (pintype "passive"))
      (node (ref "IC2") (pin "2") (pinfunction "INA-_2") (pintype "passive"))
      (node (ref "R14") (pin "1") (pinfunction "1_1") (pintype "passive"))
    )
    (net (code "49") (name "Net-(IC2B-INB-)") (class "Default")
      (node (ref "IC2") (pin "6") (pinfunction "INB-_6") (pintype "passive"))
      (node (ref "IC2") (pin "7") (pinfunction "OUTB_7") (pintype "passive"))
      (node (ref "R22") (pin "1") (pinfunction "1_1") (pintype "passive"))
    )
    (net (code "50") (name "Net-(IC2C-INC-)") (class "Default")
      (node (ref "IC2") (pin "8") (pinfunction "OUTC_8") (pintype "passive"))
      (node (ref "IC2") (pin "9") (pinfunction "INC-_9") (pintype "passive"))
      (node (ref "R18") (pin "1") (pinfunction "1_1") (pintype "passive"))
    )
    (net (code "51") (name "Net-(IC2D-IND-)") (class "Default")
      (node (ref "IC2") (pin "13") (pinfunction "IND-_13") (pintype "passive"))
      (node (ref "IC2") (pin "14") (pinfunction "OUTD_14") (pintype "passive"))
      (node (ref "R15") (pin "1") (pinfunction "1_1") (pintype "passive"))
    )
    (net (code "52") (name "Net-(U1-CLKOUT)") (class "Default")
      (node (ref "R5") (pin "1") (pinfunction "1_1") (pintype "passive"))
      (node (ref "U1") (pin "22") (pinfunction "CLKOUT_22") (pintype "output"))
    )
    (net (code "53") (name "Net-(U1-CPOUT)") (class "Default")
      (node (ref "C7") (pin "1") (pinfunction "1_1") (pintype "passive"))
      (node (ref "U1") (pin "20") (pinfunction "CPOUT_20") (pintype "passive"))
    )
    (net (code "54") (name "Net-(U1-REGOUT)") (class "Default")
      (node (ref "C9") (pin "1") (pinfunction "1_1") (pintype "passive"))
      (node (ref "U1") (pin "10") (pinfunction "REGOUT_10") (pintype "passive"))
    )
    (net (code "55") (name "Net-(U2-BST)") (class "Default")
      (node (ref "C4") (pin "1") (pinfunction "1_1") (pintype "passive"))
      (node (ref "U2") (pin "6") (pinfunction "BST_6") (pintype "input"))
    )
    (net (code "56") (name "Net-(U2-SW)") (class "Default")
      (node (ref "C4") (pin "2") (pinfunction "2_2") (pintype "passive"))
      (node (ref "L1") (pin "1") (pinfunction "1_1") (pintype "passive"))
      (node (ref "U2") (pin "5") (pinfunction "SW_5") (pintype "power_in"))
    )
    (net (code "57") (name "Net-(U3-OSC1)") (class "Default")
      (node (ref "C8") (pin "2") (pinfunction "2_2") (pintype "passive"))
      (node (ref "U3") (pin "8") (pinfunction "OSC1_8") (pintype "input"))
      (node (ref "X0") (pin "1") (pinfunction "1_1") (pintype "passive"))
    )
    (net (code "58") (name "Net-(U3-OSC2)") (class "Default")
      (node (ref "C12") (pin "2") (pinfunction "2_2") (pintype "passive"))
      (node (ref "U3") (pin "7") (pinfunction "OSC2_7") (pintype "input"))
      (node (ref "X0") (pin "3") (pinfunction "3_3") (pintype "passive"))
    )
    (net (code "59") (name "Net-(U3-RXCAN)") (class "Default")
      (node (ref "U3") (pin "2") (pinfunction "RXCAN_2") (pintype "input"))
      (node (ref "U4") (pin "4") (pinfunction "RXD_4") (pintype "output"))
    )
    (net (code "60") (name "Net-(U3-TXCAN)") (class "Default")
      (node (ref "U3") (pin "1") (pinfunction "TXCAN_1") (pintype "output"))
      (node (ref "U4") (pin "1") (pinfunction "TXD_1") (pintype "input"))
    )
    (net (code "61") (name "Net-(U3-~{RESET})") (class "Default")
      (node (ref "C6") (pin "2") (pinfunction "2_2") (pintype "passive"))
      (node (ref "D2") (pin "1") (pinfunction "1_1") (pintype "passive"))
      (node (ref "R3") (pin "2") (pinfunction "2_2") (pintype "passive"))
      (node (ref "U3") (pin "17") (pinfunction "~{RESET}_17") (pintype "input"))
    )
    (net (code "62") (name "Net-(U4-SPLIT)") (class "Default")
      (node (ref "C26") (pin "2") (pinfunction "2_2") (pintype "passive"))
      (node (ref "R10") (pin "1") (pinfunction "1_1") (pintype "passive"))
      (node (ref "R11") (pin "1") (pinfunction "1_1") (pintype "passive"))
      (node (ref "U4") (pin "5") (pinfunction "SPLIT_5") (pintype "output"))
    )
    (net (code "63") (name "Net-(U5-OSC1)") (class "Default")
      (node (ref "C18") (pin "2") (pinfunction "2_2") (pintype "passive"))
      (node (ref "U5") (pin "8") (pinfunction "OSC1_8") (pintype "input"))
      (node (ref "X1") (pin "1") (pinfunction "1_1") (pintype "passive"))
    )
    (net (code "64") (name "Net-(U5-OSC2)") (class "Default")
      (node (ref "C19") (pin "2") (pinfunction "2_2") (pintype "passive"))
      (node (ref "U5") (pin "7") (pinfunction "OSC2_7") (pintype "input"))
      (node (ref "X1") (pin "3") (pinfunction "3_3") (pintype "passive"))
    )
    (net (code "65") (name "Net-(U5-RXCAN)") (class "Default")
      (node (ref "U5") (pin "2") (pinfunction "RXCAN_2") (pintype "input"))
      (node (ref "U6") (pin "4") (pinfunction "RXD_4") (pintype "output"))
    )
    (net (code "66") (name "Net-(U5-TXCAN)") (class "Default")
      (node (ref "U5") (pin "1") (pinfunction "TXCAN_1") (pintype "output"))
      (node (ref "U6") (pin "1") (pinfunction "TXD_1") (pintype "input"))
    )
    (net (code "67") (name "Net-(U5-~{RESET})") (class "Default")
      (node (ref "C17") (pin "2") (pinfunction "2_2") (pintype "passive"))
      (node (ref "D7") (pin "1") (pinfunction "1_1") (pintype "passive"))
      (node (ref "R12") (pin "2") (pinfunction "2_2") (pintype "passive"))
      (node (ref "U5") (pin "17") (pinfunction "~{RESET}_17") (pintype "input"))
    )
    (net (code "68") (name "Net-(U6-SPLIT)") (class "Default")
      (node (ref "C27") (pin "2") (pinfunction "2_2") (pintype "passive"))
      (node (ref "R16") (pin "1") (pinfunction "1_1") (pintype "passive"))
      (node (ref "R17") (pin "1") (pinfunction "1_1") (pintype "passive"))
      (node (ref "U6") (pin "5") (pinfunction "SPLIT_5") (pintype "output"))
    )
    (net (code "69") (name "V5") (class "Default")
      (node (ref "C13") (pin "1") (pinfunction "1_1") (pintype "passive"))
      (node (ref "C14") (pin "2") (pinfunction "2_2") (pintype "passive"))
      (node (ref "C22") (pin "1") (pinfunction "1_1") (pintype "passive"))
      (node (ref "C28") (pin "2") (pinfunction "2_2") (pintype "passive"))
      (node (ref "C29") (pin "2") (pinfunction "2_2") (pintype "passive"))
      (node (ref "C5") (pin "2") (pinfunction "2_2") (pintype "passive"))
      (node (ref "IC1") (pin "4") (pinfunction "V+_4") (pintype "power_in"))
      (node (ref "IC2") (pin "4") (pinfunction "V+_4") (pintype "power_in"))
      (node (ref "L1") (pin "2") (pinfunction "2_2") (pintype "passive"))
      (node (ref "R8") (pin "2") (pinfunction "2_2") (pintype "passive"))
      (node (ref "TP3") (pin "1") (pinfunction "1_1") (pintype "passive"))
      (node (ref "U2") (pin "1") (pinfunction "FB_1") (pintype "input"))
      (node (ref "U4") (pin "3") (pinfunction "VCC_3") (pintype "power_in"))
      (node (ref "U6") (pin "3") (pinfunction "VCC_3") (pintype "power_in"))
    )
    (net (code "70") (name "VDD_12") (class "Default")
      (node (ref "C23") (pin "2") (pinfunction "2_2") (pintype "passive"))
      (node (ref "R7") (pin "2") (pinfunction "2_2") (pintype "passive"))
      (node (ref "TP2") (pin "1") (pinfunction "1_1") (pintype "passive"))
      (node (ref "U2") (pin "2") (pinfunction "EN_2") (pintype "input"))
      (node (ref "U2") (pin "3") (pinfunction "VIN_3") (pintype "power_in"))
    )
    (net (code "71") (name "unconnected-(J3-Pad1)") (class "Default")
      (node (ref "J3") (pin "1") (pinfunction "1_1") (pintype "passive+no_connect"))
    )
    (net (code "72") (name "unconnected-(J3-Pad3)") (class "Default")
      (node (ref "J3") (pin "3") (pinfunction "3_3") (pintype "passive+no_connect"))
    )
    (net (code "73") (name "unconnected-(J3-Pad4)") (class "Default")
      (node (ref "J3") (pin "4") (pinfunction "4_4") (pintype "passive+no_connect"))
    )
    (net (code "74") (name "unconnected-(J3-Pad9)") (class "Default")
      (node (ref "J3") (pin "9") (pinfunction "9_9") (pintype "passive+no_connect"))
    )
    (net (code "75") (name "unconnected-(U1-AUX_CL-Pad7)") (class "Default")
      (node (ref "U1") (pin "7") (pinfunction "AUX_CL_7") (pintype "output+no_connect"))
    )
    (net (code "76") (name "unconnected-(U1-AUX_DA-Pad6)") (class "Default")
      (node (ref "U1") (pin "6") (pinfunction "AUX_DA_6") (pintype "bidirectional+no_connect"))
    )
    (net (code "77") (name "unconnected-(U1-EP-Pad25)") (class "Default")
      (node (ref "U1") (pin "25") (pinfunction "EP_25") (pintype "power_in+no_connect"))
    )
    (net (code "78") (name "unconnected-(U1-INT-Pad12)") (class "Default")
      (node (ref "U1") (pin "12") (pinfunction "INT_12") (pintype "open_collector+no_connect"))
    )
    (net (code "79") (name "unconnected-(U1-NC-Pad2)") (class "Default")
      (node (ref "U1") (pin "2") (pinfunction "NC_2") (pintype "passive+no_connect"))
    )
    (net (code "80") (name "unconnected-(U1-NC-Pad3)") (class "Default")
      (node (ref "U1") (pin "3") (pinfunction "NC_3") (pintype "passive+no_connect"))
    )
    (net (code "81") (name "unconnected-(U1-NC-Pad4)") (class "Default")
      (node (ref "U1") (pin "4") (pinfunction "NC_4") (pintype "passive+no_connect"))
    )
    (net (code "82") (name "unconnected-(U1-NC-Pad5)") (class "Default")
      (node (ref "U1") (pin "5") (pinfunction "NC_5") (pintype "passive+no_connect"))
    )
    (net (code "83") (name "unconnected-(U1-NC-Pad14)") (class "Default")
      (node (ref "U1") (pin "14") (pinfunction "NC_14") (pintype "passive+no_connect"))
    )
    (net (code "84") (name "unconnected-(U1-NC-Pad15)") (class "Default")
      (node (ref "U1") (pin "15") (pinfunction "NC_15") (pintype "passive+no_connect"))
    )
    (net (code "85") (name "unconnected-(U1-NC-Pad16)") (class "Default")
      (node (ref "U1") (pin "16") (pinfunction "NC_16") (pintype "passive+no_connect"))
    )
    (net (code "86") (name "unconnected-(U1-NC-Pad17)") (class "Default")
      (node (ref "U1") (pin "17") (pinfunction "NC_17") (pintype "passive+no_connect"))
    )
    (net (code "87") (name "unconnected-(U1-RESV-Pad19)") (class "Default")
      (node (ref "U1") (pin "19") (pinfunction "RESV_19") (pintype "passive+no_connect"))
    )
    (net (code "88") (name "unconnected-(U1-RESV-Pad21)") (class "Default")
      (node (ref "U1") (pin "21") (pinfunction "RESV_21") (pintype "passive+no_connect"))
    )
    (net (code "89") (name "unconnected-(U3-CLKOUT{slash}SOF-Pad3)") (class "Default")
      (node (ref "U3") (pin "3") (pinfunction "CLKOUT/SOF_3") (pintype "output+no_connect"))
    )
    (net (code "90") (name "unconnected-(U3-~{RX0BF}-Pad11)") (class "Default")
      (node (ref "U3") (pin "11") (pinfunction "~{RX0BF}_11") (pintype "input+no_connect"))
    )
    (net (code "91") (name "unconnected-(U3-~{RX1BF}-Pad10)") (class "Default")
      (node (ref "U3") (pin "10") (pinfunction "~{RX1BF}_10") (pintype "input+no_connect"))
    )
    (net (code "92") (name "unconnected-(U3-~{TX0RTS}-Pad4)") (class "Default")
      (node (ref "U3") (pin "4") (pinfunction "~{TX0RTS}_4") (pintype "output+no_connect"))
    )
    (net (code "93") (name "unconnected-(U3-~{TX1RTS}-Pad5)") (class "Default")
      (node (ref "U3") (pin "5") (pinfunction "~{TX1RTS}_5") (pintype "output+no_connect"))
    )
    (net (code "94") (name "unconnected-(U3-~{TX2RTS}-Pad6)") (class "Default")
      (node (ref "U3") (pin "6") (pinfunction "~{TX2RTS}_6") (pintype "output+no_connect"))
    )
    (net (code "95") (name "unconnected-(U5-CLKOUT{slash}SOF-Pad3)") (class "Default")
      (node (ref "U5") (pin "3") (pinfunction "CLKOUT/SOF_3") (pintype "output+no_connect"))
    )
    (net (code "96") (name "unconnected-(U5-~{RX0BF}-Pad11)") (class "Default")
      (node (ref "U5") (pin "11") (pinfunction "~{RX0BF}_11") (pintype "input+no_connect"))
    )
    (net (code "97") (name "unconnected-(U5-~{RX1BF}-Pad10)") (class "Default")
      (node (ref "U5") (pin "10") (pinfunction "~{RX1BF}_10") (pintype "input+no_connect"))
    )
    (net (code "98") (name "unconnected-(U5-~{TX0RTS}-Pad4)") (class "Default")
      (node (ref "U5") (pin "4") (pinfunction "~{TX0RTS}_4") (pintype "output+no_connect"))
    )
    (net (code "99") (name "unconnected-(U5-~{TX1RTS}-Pad5)") (class "Default")
      (node (ref "U5") (pin "5") (pinfunction "~{TX1RTS}_5") (pintype "output+no_connect"))
    )
    (net (code "100") (name "unconnected-(U5-~{TX2RTS}-Pad6)") (class "Default")
      (node (ref "U5") (pin "6") (pinfunction "~{TX2RTS}_6") (pintype "output+no_connect"))
    )
  )
)
